# mc-v2-sch.net
KiCad netlist of a schematic drawn in EAGLE
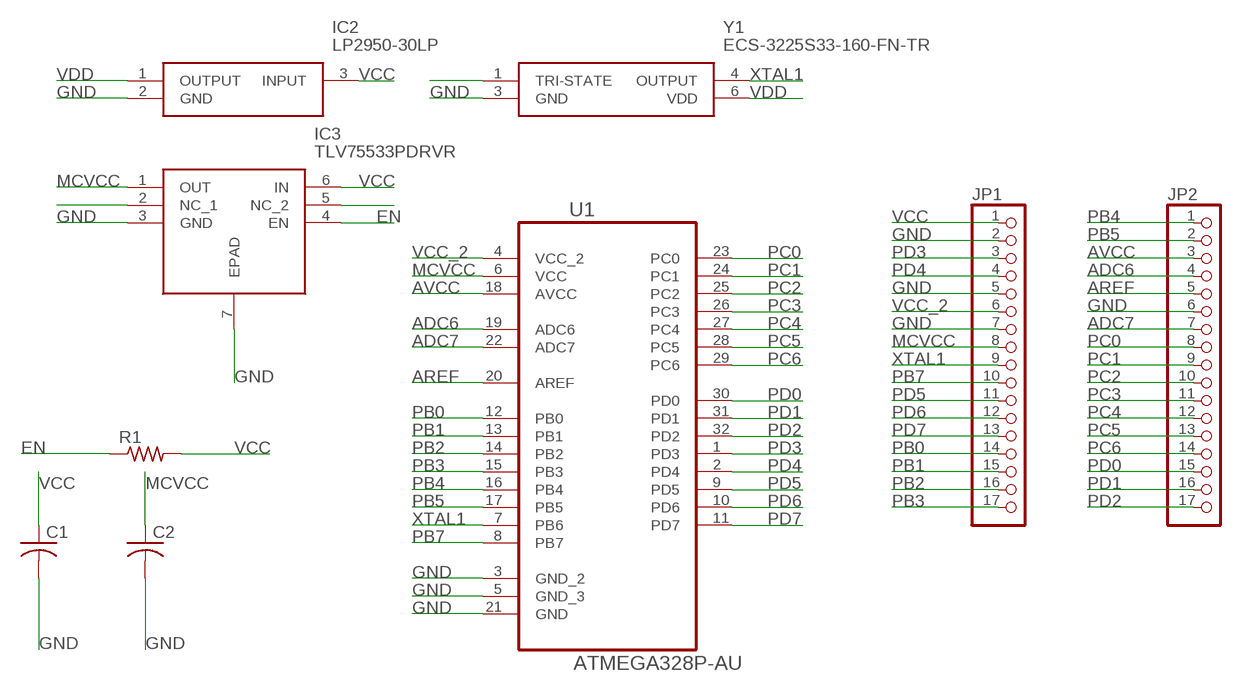
[diagram p0: schematic, sheet 1]

(export (version "E")
  (design (tool "Eeschema 10.0.6"))
  (components
    (comp (ref "C1")
      (value "C-USC1206")
      (footprint "eagle-import:C1206")
      (libsource (lib "eagle-import") (part "C-USC1206"))
    )
    (comp (ref "C2")
      (value "C-USC1206")
      (footprint "eagle-import:C1206")
      (libsource (lib "eagle-import") (part "C-USC1206"))
    )
    (comp (ref "IC2")
      (value "LP2950-30LP")
      (footprint "eagle-import:LP0003A")
      (fields (field (name "MOUSER_PART_NUMBER") "595-LP2950-30LP") (field (name "RS_PART_NUMBER") "7620437"))
      (libsource (lib "eagle-import") (part "LP2950-30LP"))
    )
    (comp (ref "IC3")
      (value "TLV75533PDRVR")
      (footprint "eagle-import:SON65P200X200X80-7N")
      (fields (field (name "MOUSER_PART_NUMBER") "595-TLV75533PDRVR"))
      (libsource (lib "eagle-import") (part "TLV75533PDRVR"))
    )
    (comp (ref "JP1")
      (value "PINHD-1X17")
      (footprint "eagle-import:1X17")
      (libsource (lib "eagle-import") (part "PINHD-1X17"))
    )
    (comp (ref "JP2")
      (value "PINHD-1X17")
      (footprint "eagle-import:1X17")
      (libsource (lib "eagle-import") (part "PINHD-1X17"))
    )
    (comp (ref "R1")
      (value "R-US_R0603")
      (footprint "eagle-import:R0603")
      (libsource (lib "eagle-import") (part "R-US_R0603"))
    )
    (comp (ref "U1")
      (value "ATMEGA328P-AU")
      (footprint "eagle-import:QFP80P900X900X120-32N")
      (libsource (lib "eagle-import") (part "ATMEGA328P-AU"))
    )
    (comp (ref "Y1")
      (value "ECS-3225S33-160-FN-TR")
      (footprint "eagle-import:ECS3225S33200FNTR")
      (fields (field (name "MOUSER_PART_NUMBER") "520-3225S33-160-FNT"))
      (libsource (lib "eagle-import") (part "ECS-3225S33-160-FN-TR"))
    )
  )
  (nets
    (net (code "1") (name "/ADC6") (class "Default")
      (node (ref "JP2") (pin "4") (pinfunction "4_4") (pintype "passive"))
      (node (ref "U1") (pin "19") (pinfunction "ADC6_19") (pintype "input"))
    )
    (net (code "2") (name "/ADC7") (class "Default")
      (node (ref "JP2") (pin "7") (pinfunction "7_7") (pintype "passive"))
      (node (ref "U1") (pin "22") (pinfunction "ADC7_22") (pintype "input"))
    )
    (net (code "3") (name "/AREF") (class "Default")
      (node (ref "JP2") (pin "5") (pinfunction "5_5") (pintype "passive"))
      (node (ref "U1") (pin "20") (pinfunction "AREF_20") (pintype "input"))
    )
    (net (code "4") (name "/AVCC") (class "Default")
      (node (ref "JP2") (pin "3") (pinfunction "3_3") (pintype "passive"))
      (node (ref "U1") (pin "18") (pinfunction "AVCC_18") (pintype "power_in"))
    )
    (net (code "5") (name "/EN") (class "Default")
      (node (ref "IC3") (pin "4") (pinfunction "EN_4") (pintype "bidirectional"))
      (node (ref "R1") (pin "1") (pinfunction "1_1") (pintype "passive"))
    )
    (net (code "6") (name "/GND") (class "Default")
      (node (ref "C1") (pin "2") (pinfunction "2_2") (pintype "passive"))
      (node (ref "C2") (pin "2") (pinfunction "2_2") (pintype "passive"))
      (node (ref "IC2") (pin "2") (pinfunction "GND_2") (pintype "bidirectional"))
      (node (ref "IC3") (pin "3") (pinfunction "GND_3") (pintype "bidirectional"))
      (node (ref "IC3") (pin "7") (pinfunction "EPAD_7") (pintype "bidirectional"))
      (node (ref "JP1") (pin "2") (pinfunction "2_2") (pintype "passive"))
      (node (ref "JP1") (pin "5") (pinfunction "5_5") (pintype "passive"))
      (node (ref "JP1") (pin "7") (pinfunction "7_7") (pintype "passive"))
      (node (ref "JP2") (pin "6") (pinfunction "6_6") (pintype "passive"))
      (node (ref "U1") (pin "21") (pinfunction "GND_21") (pintype "passive"))
      (node (ref "U1") (pin "3") (pinfunction "GND_2_3") (pintype "passive"))
      (node (ref "U1") (pin "5") (pinfunction "GND_3_5") (pintype "passive"))
      (node (ref "Y1") (pin "3") (pinfunction "GND_3") (pintype "bidirectional"))
    )
    (net (code "7") (name "/MCVCC") (class "Default")
      (node (ref "C2") (pin "1") (pinfunction "1_1") (pintype "passive"))
      (node (ref "IC3") (pin "1") (pinfunction "OUT_1") (pintype "bidirectional"))
      (node (ref "JP1") (pin "8") (pinfunction "8_8") (pintype "passive"))
      (node (ref "U1") (pin "6") (pinfunction "VCC_6") (pintype "power_in"))
    )
    (net (code "8") (name "/PB0") (class "Default")
      (node (ref "JP1") (pin "14") (pinfunction "14_14") (pintype "passive"))
      (node (ref "U1") (pin "12") (pinfunction "PB0_12") (pintype "bidirectional"))
    )
    (net (code "9") (name "/PB1") (class "Default")
      (node (ref "JP1") (pin "15") (pinfunction "15_15") (pintype "passive"))
      (node (ref "U1") (pin "13") (pinfunction "PB1_13") (pintype "bidirectional"))
    )
    (net (code "10") (name "/PB2") (class "Default")
      (node (ref "JP1") (pin "16") (pinfunction "16_16") (pintype "passive"))
      (node (ref "U1") (pin "14") (pinfunction "PB2_14") (pintype "bidirectional"))
    )
    (net (code "11") (name "/PB3") (class "Default")
      (node (ref "JP1") (pin "17") (pinfunction "17_17") (pintype "passive"))
      (node (ref "U1") (pin "15") (pinfunction "PB3_15") (pintype "bidirectional"))
    )
    (net (code "12") (name "/PB4") (class "Default")
      (node (ref "JP2") (pin "1") (pinfunction "1_1") (pintype "passive"))
      (node (ref "U1") (pin "16") (pinfunction "PB4_16") (pintype "bidirectional"))
    )
    (net (code "13") (name "/PB5") (class "Default")
      (node (ref "JP2") (pin "2") (pinfunction "2_2") (pintype "passive"))
      (node (ref "U1") (pin "17") (pinfunction "PB5_17") (pintype "bidirectional"))
    )
    (net (code "14") (name "/PB7") (class "Default")
      (node (ref "JP1") (pin "10") (pinfunction "10_10") (pintype "passive"))
      (node (ref "U1") (pin "8") (pinfunction "PB7_8") (pintype "bidirectional"))
    )
    (net (code "15") (name "/PC0") (class "Default")
      (node (ref "JP2") (pin "8") (pinfunction "8_8") (pintype "passive"))
      (node (ref "U1") (pin "23") (pinfunction "PC0_23") (pintype "bidirectional"))
    )
    (net (code "16") (name "/PC1") (class "Default")
      (node (ref "JP2") (pin "9") (pinfunction "9_9") (pintype "passive"))
      (node (ref "U1") (pin "24") (pinfunction "PC1_24") (pintype "bidirectional"))
    )
    (net (code "17") (name "/PC2") (class "Default")
      (node (ref "JP2") (pin "10") (pinfunction "10_10") (pintype "passive"))
      (node (ref "U1") (pin "25") (pinfunction "PC2_25") (pintype "bidirectional"))
    )
    (net (code "18") (name "/PC3") (class "Default")
      (node (ref "JP2") (pin "11") (pinfunction "11_11") (pintype "passive"))
      (node (ref "U1") (pin "26") (pinfunction "PC3_26") (pintype "bidirectional"))
    )
    (net (code "19") (name "/PC4") (class "Default")
      (node (ref "JP2") (pin "12") (pinfunction "12_12") (pintype "passive"))
      (node (ref "U1") (pin "27") (pinfunction "PC4_27") (pintype "bidirectional"))
    )
    (net (code "20") (name "/PC5") (class "Default")
      (node (ref "JP2") (pin "13") (pinfunction "13_13") (pintype "passive"))
      (node (ref "U1") (pin "28") (pinfunction "PC5_28") (pintype "bidirectional"))
    )
    (net (code "21") (name "/PC6") (class "Default")
      (node (ref "JP2") (pin "14") (pinfunction "14_14") (pintype "passive"))
      (node (ref "U1") (pin "29") (pinfunction "PC6_29") (pintype "bidirectional"))
    )
    (net (code "22") (name "/PD0") (class "Default")
      (node (ref "JP2") (pin "15") (pinfunction "15_15") (pintype "passive"))
      (node (ref "U1") (pin "30") (pinfunction "PD0_30") (pintype "bidirectional"))
    )
    (net (code "23") (name "/PD1") (class "Default")
      (node (ref "JP2") (pin "16") (pinfunction "16_16") (pintype "passive"))
      (node (ref "U1") (pin "31") (pinfunction "PD1_31") (pintype "bidirectional"))
    )
    (net (code "24") (name "/PD2") (class "Default")
      (node (ref "JP2") (pin "17") (pinfunction "17_17") (pintype "passive"))
      (node (ref "U1") (pin "32") (pinfunction "PD2_32") (pintype "bidirectional"))
    )
    (net (code "25") (name "/PD3") (class "Default")
      (node (ref "JP1") (pin "3") (pinfunction "3_3") (pintype "passive"))
      (node (ref "U1") (pin "1") (pinfunction "PD3_1") (pintype "bidirectional"))
    )
    (net (code "26") (name "/PD4") (class "Default")
      (node (ref "JP1") (pin "4") (pinfunction "4_4") (pintype "passive"))
      (node (ref "U1") (pin "2") (pinfunction "PD4_2") (pintype "bidirectional"))
    )
    (net (code "27") (name "/PD5") (class "Default")
      (node (ref "JP1") (pin "11") (pinfunction "11_11") (pintype "passive"))
      (node (ref "U1") (pin "9") (pinfunction "PD5_9") (pintype "bidirectional"))
    )
    (net (code "28") (name "/PD6") (class "Default")
      (node (ref "JP1") (pin "12") (pinfunction "12_12") (pintype "passive"))
      (node (ref "U1") (pin "10") (pinfunction "PD6_10") (pintype "bidirectional"))
    )
    (net (code "29") (name "/PD7") (class "Default")
      (node (ref "JP1") (pin "13") (pinfunction "13_13") (pintype "passive"))
      (node (ref "U1") (pin "11") (pinfunction "PD7_11") (pintype "bidirectional"))
    )
    (net (code "30") (name "/VCC") (class "Default")
      (node (ref "C1") (pin "1") (pinfunction "1_1") (pintype "passive"))
      (node (ref "IC2") (pin "3") (pinfunction "INPUT_3") (pintype "bidirectional"))
      (node (ref "IC3") (pin "6") (pinfunction "IN_6") (pintype "bidirectional"))
      (node (ref "JP1") (pin "1") (pinfunction "1_1") (pintype "passive"))
      (node (ref "R1") (pin "2") (pinfunction "2_2") (pintype "passive"))
    )
    (net (code "31") (name "/VCC_2") (class "Default")
      (node (ref "JP1") (pin "6") (pinfunction "6_6") (pintype "passive"))
      (node (ref "U1") (pin "4") (pinfunction "VCC_2_4") (pintype "power_in"))
    )
    (net (code "32") (name "/VDD") (class "Default")
      (node (ref "IC2") (pin "1") (pinfunction "OUTPUT_1") (pintype "bidirectional"))
      (node (ref "Y1") (pin "6") (pinfunction "VDD_6") (pintype "bidirectional"))
    )
    (net (code "33") (name "/XTAL1") (class "Default")
      (node (ref "JP1") (pin "9") (pinfunction "9_9") (pintype "passive"))
      (node (ref "U1") (pin "7") (pinfunction "PB6_7") (pintype "bidirectional"))
      (node (ref "Y1") (pin "4") (pinfunction "OUTPUT_4") (pintype "bidirectional"))
    )
    (net (code "34") (name "unconnected-(IC3-NC_1-Pad2)") (class "Default")
      (node (ref "IC3") (pin "2") (pinfunction "NC_1_2") (pintype "bidirectional"))
    )
    (net (code "35") (name "unconnected-(IC3-NC_2-Pad5)") (class "Default")
      (node (ref "IC3") (pin "5") (pinfunction "NC_2_5") (pintype "bidirectional"))
    )
    (net (code "36") (name "unconnected-(Y1-TRI-STATE-Pad1)") (class "Default")
      (node (ref "Y1") (pin "1") (pinfunction "TRI-STATE_1") (pintype "bidirectional"))
    )
  )
)
